# MOSFETboard.net
KiCad netlist of a schematic drawn in EAGLE
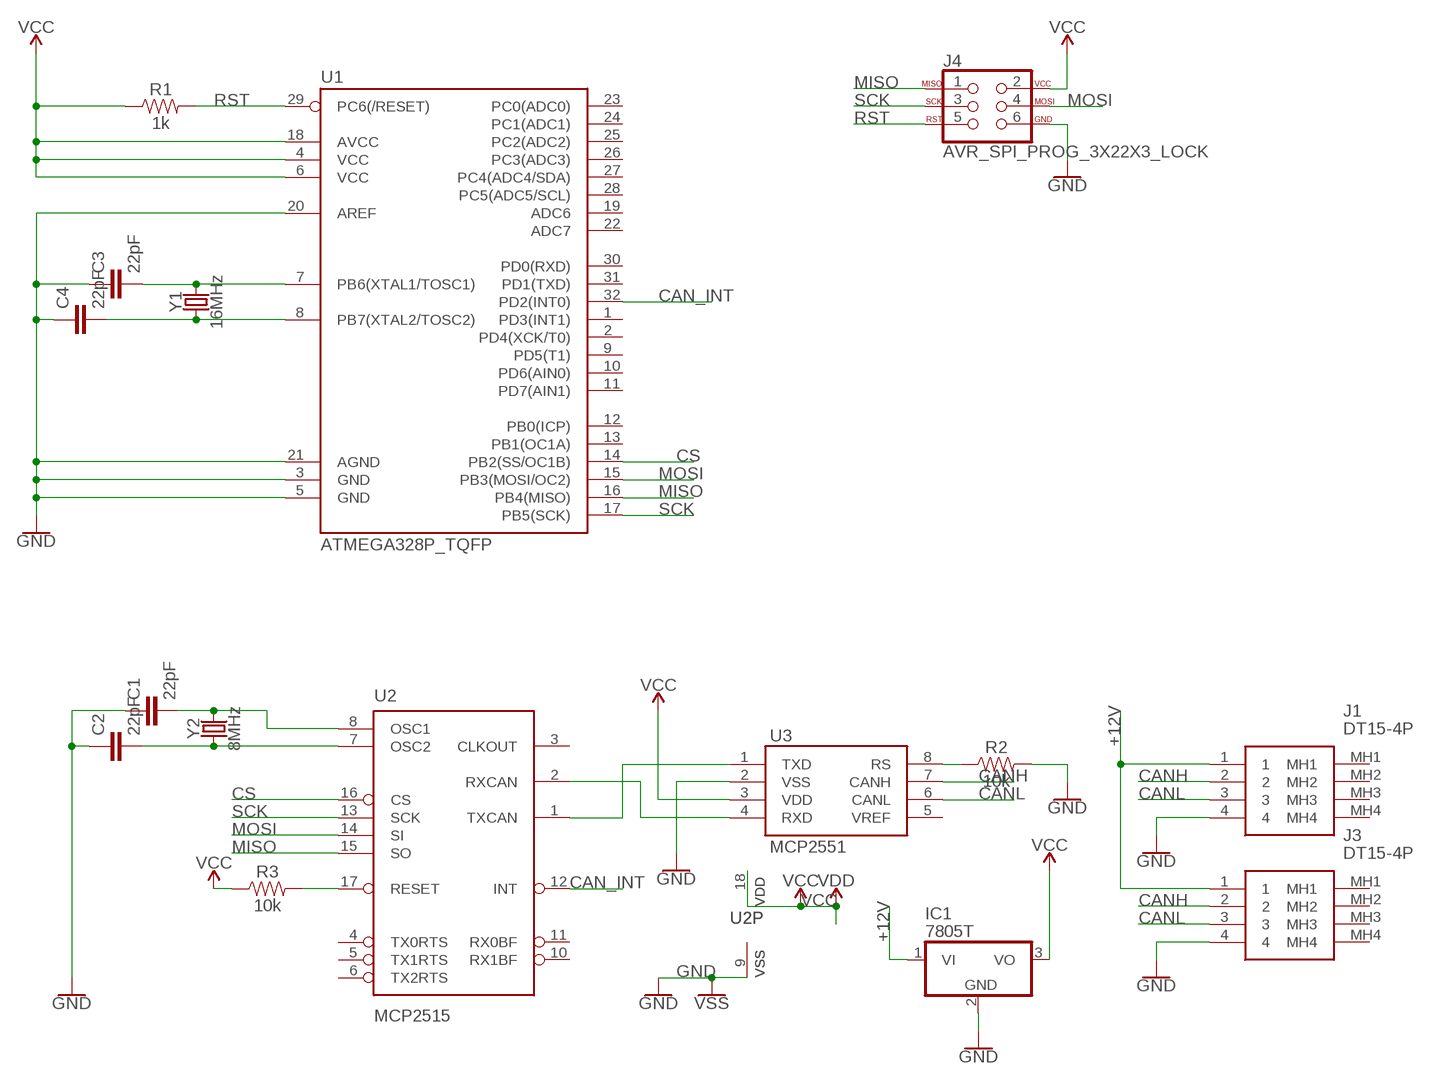
[diagram p0: schematic, sheet 1, part 1 of 2]
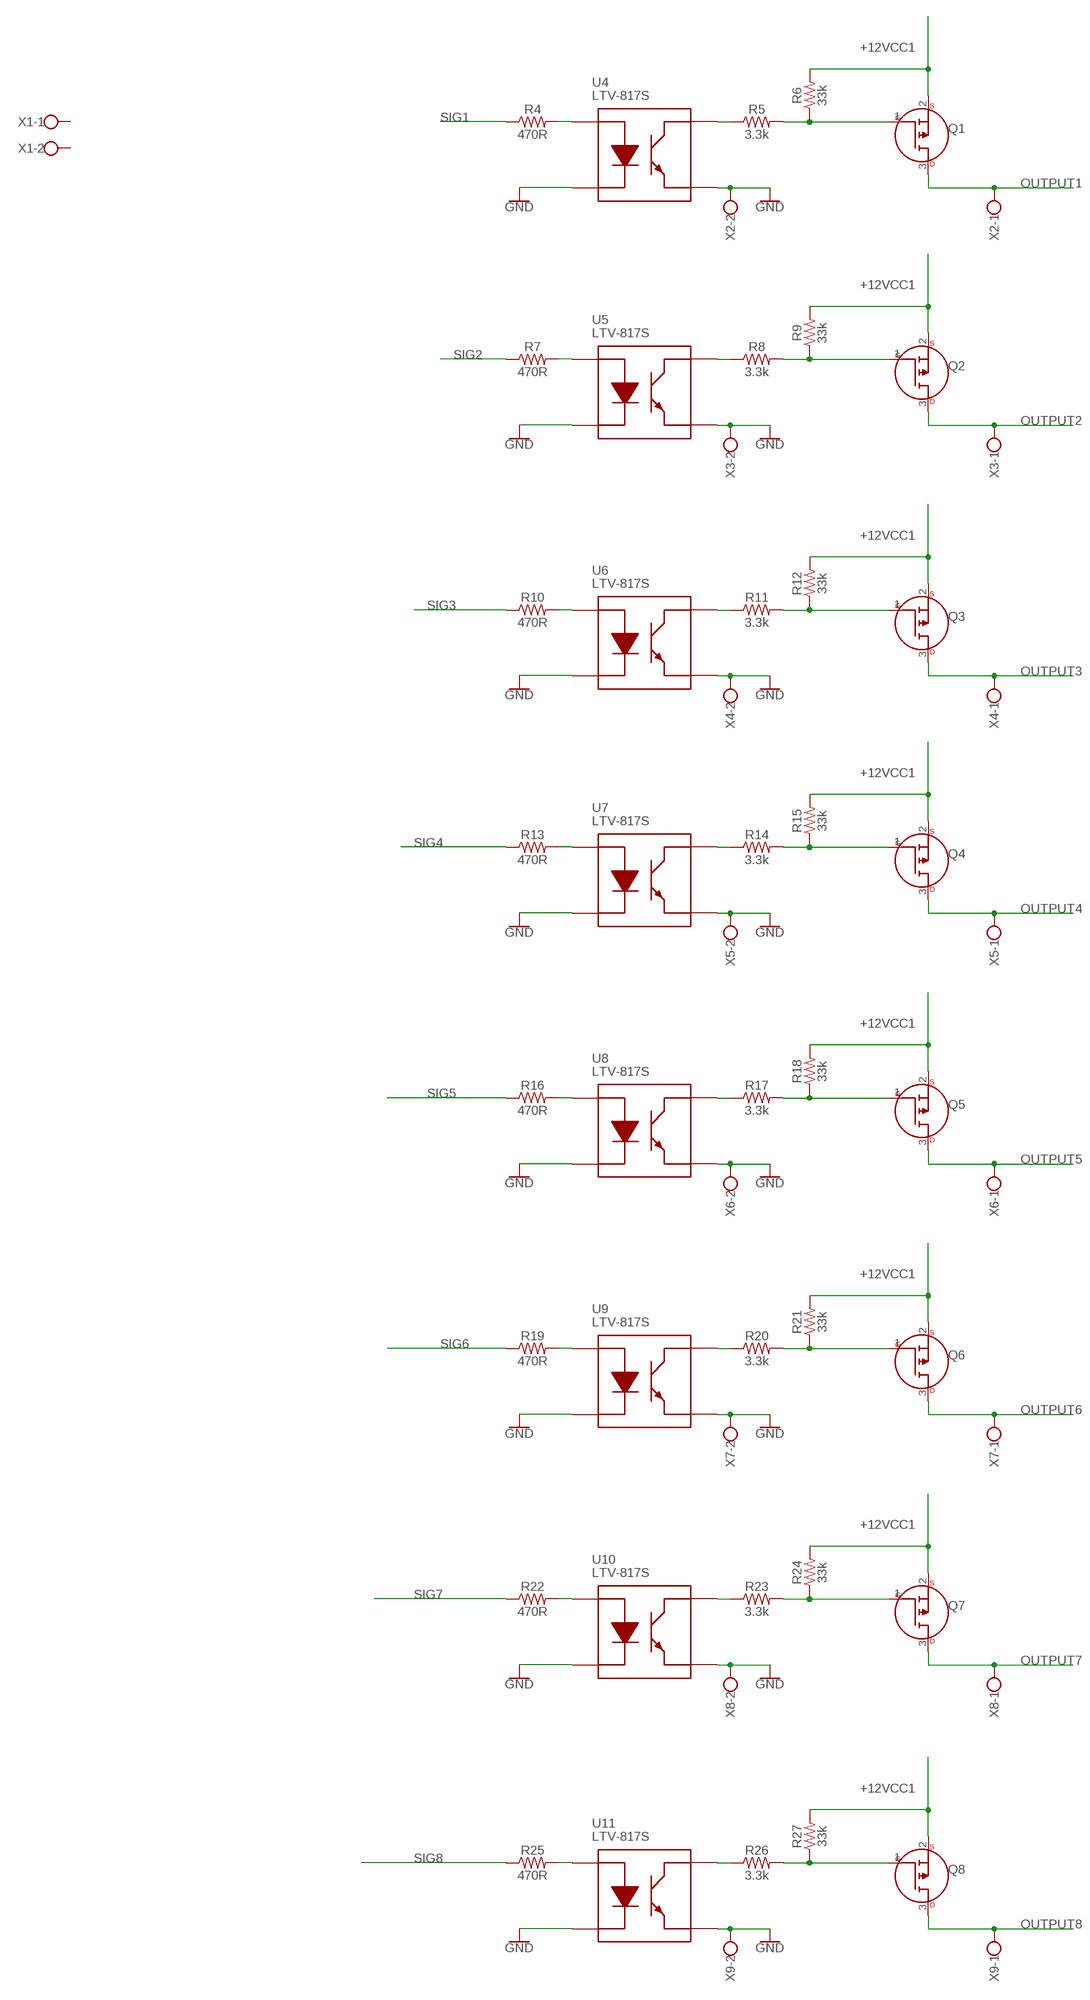
[diagram p1: schematic, sheet 1, part 2 of 2]

(export (version "E")
  (design (tool "Eeschema 10.0.6"))
  (components
    (comp (ref "C1")
      (value "22pF")
      (footprint "eagle-import:0603")
      (libsource (lib "eagle-import") (part "22PF-0603-50V-5%"))
    )
    (comp (ref "C2")
      (value "22pF")
      (footprint "eagle-import:0603")
      (libsource (lib "eagle-import") (part "22PF-0603-50V-5%"))
    )
    (comp (ref "C3")
      (value "22pF")
      (footprint "eagle-import:0603")
      (libsource (lib "eagle-import") (part "22PF-0603-50V-5%"))
    )
    (comp (ref "C4")
      (value "22pF")
      (footprint "eagle-import:0603")
      (libsource (lib "eagle-import") (part "22PF-0603-50V-5%"))
    )
    (comp (ref "IC1")
      (value "7805T")
      (footprint "eagle-import:TO220H")
      (libsource (lib "eagle-import") (part "78T05"))
    )
    (comp (ref "J1")
      (value "DT15-4P")
      (footprint "eagle-import:DT154P")
      (fields (field (name "MOUSER_PART_NUMBER") "571-DT15-4P"))
      (libsource (lib "eagle-import") (part "DT15-4P"))
    )
    (comp (ref "J3")
      (value "DT15-4P")
      (footprint "eagle-import:DT154P")
      (fields (field (name "MOUSER_PART_NUMBER") "571-DT15-4P"))
      (libsource (lib "eagle-import") (part "DT15-4P"))
    )
    (comp (ref "J4")
      (value "AVR_SPI_PROG_3X22X3_LOCK")
      (footprint "eagle-import:2X3_LOCK")
      (libsource (lib "eagle-import") (part "AVR_SPI_PROG_3X22X3_LOCK"))
    )
    (comp (ref "Q1")
      (value "IRFR9014TRPBF-BE3")
      (footprint "eagle-import:IRFR9014TRPBFBE3")
      (fields (field (name "MOUSER_PART_NUMBER") "78-IRFR9014TRPBF-BE3"))
      (libsource (lib "eagle-import") (part "IRFR9014TRPBF-BE3"))
    )
    (comp (ref "Q2")
      (value "IRFR9014TRPBF-BE3")
      (footprint "eagle-import:IRFR9014TRPBFBE3")
      (fields (field (name "MOUSER_PART_NUMBER") "78-IRFR9014TRPBF-BE3"))
      (libsource (lib "eagle-import") (part "IRFR9014TRPBF-BE3"))
    )
    (comp (ref "Q3")
      (value "IRFR9014TRPBF-BE3")
      (footprint "eagle-import:IRFR9014TRPBFBE3")
      (fields (field (name "MOUSER_PART_NUMBER") "78-IRFR9014TRPBF-BE3"))
      (libsource (lib "eagle-import") (part "IRFR9014TRPBF-BE3"))
    )
    (comp (ref "Q4")
      (value "IRFR9014TRPBF-BE3")
      (footprint "eagle-import:IRFR9014TRPBFBE3")
      (fields (field (name "MOUSER_PART_NUMBER") "78-IRFR9014TRPBF-BE3"))
      (libsource (lib "eagle-import") (part "IRFR9014TRPBF-BE3"))
    )
    (comp (ref "Q5")
      (value "IRFR9014TRPBF-BE3")
      (footprint "eagle-import:IRFR9014TRPBFBE3")
      (fields (field (name "MOUSER_PART_NUMBER") "78-IRFR9014TRPBF-BE3"))
      (libsource (lib "eagle-import") (part "IRFR9014TRPBF-BE3"))
    )
    (comp (ref "Q6")
      (value "IRFR9014TRPBF-BE3")
      (footprint "eagle-import:IRFR9014TRPBFBE3")
      (fields (field (name "MOUSER_PART_NUMBER") "78-IRFR9014TRPBF-BE3"))
      (libsource (lib "eagle-import") (part "IRFR9014TRPBF-BE3"))
    )
    (comp (ref "Q7")
      (value "IRFR9014TRPBF-BE3")
      (footprint "eagle-import:IRFR9014TRPBFBE3")
      (fields (field (name "MOUSER_PART_NUMBER") "78-IRFR9014TRPBF-BE3"))
      (libsource (lib "eagle-import") (part "IRFR9014TRPBF-BE3"))
    )
    (comp (ref "Q8")
      (value "IRFR9014TRPBF-BE3")
      (footprint "eagle-import:IRFR9014TRPBFBE3")
      (fields (field (name "MOUSER_PART_NUMBER") "78-IRFR9014TRPBF-BE3"))
      (libsource (lib "eagle-import") (part "IRFR9014TRPBF-BE3"))
    )
    (comp (ref "R1")
      (value "1k")
      (footprint "eagle-import:0603")
      (libsource (lib "eagle-import") (part "1KOHM-0603-1/10W-1%"))
    )
    (comp (ref "R2")
      (value "10k")
      (footprint "eagle-import:0603")
      (libsource (lib "eagle-import") (part "1KOHM-0603-1/10W-1%"))
    )
    (comp (ref "R3")
      (value "10k")
      (footprint "eagle-import:0603")
      (libsource (lib "eagle-import") (part "1KOHM-0603-1/10W-1%"))
    )
    (comp (ref "R4")
      (value "470R")
      (footprint "eagle-import:0603")
      (libsource (lib "eagle-import") (part "1KOHM-0603-1/10W-1%"))
    )
    (comp (ref "R5")
      (value "3.3k")
      (footprint "eagle-import:0603")
      (libsource (lib "eagle-import") (part "1KOHM-0603-1/10W-1%"))
    )
    (comp (ref "R6")
      (value "33k")
      (footprint "eagle-import:0603")
      (libsource (lib "eagle-import") (part "1KOHM-0603-1/10W-1%"))
    )
    (comp (ref "R7")
      (value "470R")
      (footprint "eagle-import:0603")
      (libsource (lib "eagle-import") (part "1KOHM-0603-1/10W-1%"))
    )
    (comp (ref "R8")
      (value "3.3k")
      (footprint "eagle-import:0603")
      (libsource (lib "eagle-import") (part "1KOHM-0603-1/10W-1%"))
    )
    (comp (ref "R9")
      (value "33k")
      (footprint "eagle-import:0603")
      (libsource (lib "eagle-import") (part "1KOHM-0603-1/10W-1%"))
    )
    (comp (ref "R10")
      (value "470R")
      (footprint "eagle-import:0603")
      (libsource (lib "eagle-import") (part "1KOHM-0603-1/10W-1%"))
    )
    (comp (ref "R11")
      (value "3.3k")
      (footprint "eagle-import:0603")
      (libsource (lib "eagle-import") (part "1KOHM-0603-1/10W-1%"))
    )
    (comp (ref "R12")
      (value "33k")
      (footprint "eagle-import:0603")
      (libsource (lib "eagle-import") (part "1KOHM-0603-1/10W-1%"))
    )
    (comp (ref "R13")
      (value "470R")
      (footprint "eagle-import:0603")
      (libsource (lib "eagle-import") (part "1KOHM-0603-1/10W-1%"))
    )
    (comp (ref "R14")
      (value "3.3k")
      (footprint "eagle-import:0603")
      (libsource (lib "eagle-import") (part "1KOHM-0603-1/10W-1%"))
    )
    (comp (ref "R15")
      (value "33k")
      (footprint "eagle-import:0603")
      (libsource (lib "eagle-import") (part "1KOHM-0603-1/10W-1%"))
    )
    (comp (ref "R16")
      (value "470R")
      (footprint "eagle-import:0603")
      (libsource (lib "eagle-import") (part "1KOHM-0603-1/10W-1%"))
    )
    (comp (ref "R17")
      (value "3.3k")
      (footprint "eagle-import:0603")
      (libsource (lib "eagle-import") (part "1KOHM-0603-1/10W-1%"))
    )
    (comp (ref "R18")
      (value "33k")
      (footprint "eagle-import:0603")
      (libsource (lib "eagle-import") (part "1KOHM-0603-1/10W-1%"))
    )
    (comp (ref "R19")
      (value "470R")
      (footprint "eagle-import:0603")
      (libsource (lib "eagle-import") (part "1KOHM-0603-1/10W-1%"))
    )
    (comp (ref "R20")
      (value "3.3k")
      (footprint "eagle-import:0603")
      (libsource (lib "eagle-import") (part "1KOHM-0603-1/10W-1%"))
    )
    (comp (ref "R21")
      (value "33k")
      (footprint "eagle-import:0603")
      (libsource (lib "eagle-import") (part "1KOHM-0603-1/10W-1%"))
    )
    (comp (ref "R22")
      (value "470R")
      (footprint "eagle-import:0603")
      (libsource (lib "eagle-import") (part "1KOHM-0603-1/10W-1%"))
    )
    (comp (ref "R23")
      (value "3.3k")
      (footprint "eagle-import:0603")
      (libsource (lib "eagle-import") (part "1KOHM-0603-1/10W-1%"))
    )
    (comp (ref "R24")
      (value "33k")
      (footprint "eagle-import:0603")
      (libsource (lib "eagle-import") (part "1KOHM-0603-1/10W-1%"))
    )
    (comp (ref "R25")
      (value "470R")
      (footprint "eagle-import:0603")
      (libsource (lib "eagle-import") (part "1KOHM-0603-1/10W-1%"))
    )
    (comp (ref "R26")
      (value "3.3k")
      (footprint "eagle-import:0603")
      (libsource (lib "eagle-import") (part "1KOHM-0603-1/10W-1%"))
    )
    (comp (ref "R27")
      (value "33k")
      (footprint "eagle-import:0603")
      (libsource (lib "eagle-import") (part "1KOHM-0603-1/10W-1%"))
    )
    (comp (ref "U1")
      (value "ATMEGA328P_TQFP")
      (footprint "eagle-import:TQFP32-08")
      (libsource (lib "eagle-import") (part "ATMEGA328P_TQFP"))
    )
    (comp (ref "U2")
      (value "MCP2515")
      (footprint "eagle-import:SO18W")
      (libsource (lib "eagle-import") (part "MCP2515(MCP2510)SO"))
    )
    (comp (ref "U3")
      (value "MCP2551")
      (footprint "eagle-import:SO08")
      (libsource (lib "eagle-import") (part "MCP2551"))
    )
    (comp (ref "U4")
      (value "LTV-817S")
      (footprint "eagle-import:SOP254P1016X460-4N")
      (fields (field (name "MOUSER_PART_NUMBER") "859-LTV-817S"))
      (libsource (lib "eagle-import") (part "LTV-817S"))
    )
    (comp (ref "U5")
      (value "LTV-817S")
      (footprint "eagle-import:SOP254P1016X460-4N")
      (fields (field (name "MOUSER_PART_NUMBER") "859-LTV-817S"))
      (libsource (lib "eagle-import") (part "LTV-817S"))
    )
    (comp (ref "U6")
      (value "LTV-817S")
      (footprint "eagle-import:SOP254P1016X460-4N")
      (fields (field (name "MOUSER_PART_NUMBER") "859-LTV-817S"))
      (libsource (lib "eagle-import") (part "LTV-817S"))
    )
    (comp (ref "U7")
      (value "LTV-817S")
      (footprint "eagle-import:SOP254P1016X460-4N")
      (fields (field (name "MOUSER_PART_NUMBER") "859-LTV-817S"))
      (libsource (lib "eagle-import") (part "LTV-817S"))
    )
    (comp (ref "U8")
      (value "LTV-817S")
      (footprint "eagle-import:SOP254P1016X460-4N")
      (fields (field (name "MOUSER_PART_NUMBER") "859-LTV-817S"))
      (libsource (lib "eagle-import") (part "LTV-817S"))
    )
    (comp (ref "U9")
      (value "LTV-817S")
      (footprint "eagle-import:SOP254P1016X460-4N")
      (fields (field (name "MOUSER_PART_NUMBER") "859-LTV-817S"))
      (libsource (lib "eagle-import") (part "LTV-817S"))
    )
    (comp (ref "U10")
      (value "LTV-817S")
      (footprint "eagle-import:SOP254P1016X460-4N")
      (fields (field (name "MOUSER_PART_NUMBER") "859-LTV-817S"))
      (libsource (lib "eagle-import") (part "LTV-817S"))
    )
    (comp (ref "U11")
      (value "LTV-817S")
      (footprint "eagle-import:SOP254P1016X460-4N")
      (fields (field (name "MOUSER_PART_NUMBER") "859-LTV-817S"))
      (libsource (lib "eagle-import") (part "LTV-817S"))
    )
    (comp (ref "X1")
      (value "W237-102")
      (footprint "eagle-import:W237-102")
      (fields (field (name "MPN") "237-102"))
      (libsource (lib "eagle-import") (part "W237-102"))
    )
    (comp (ref "X2")
      (value "W237-102")
      (footprint "eagle-import:W237-102")
      (fields (field (name "MPN") "237-102"))
      (libsource (lib "eagle-import") (part "W237-102"))
    )
    (comp (ref "X3")
      (value "W237-102")
      (footprint "eagle-import:W237-102")
      (fields (field (name "MPN") "237-102"))
      (libsource (lib "eagle-import") (part "W237-102"))
    )
    (comp (ref "X4")
      (value "W237-102")
      (footprint "eagle-import:W237-102")
      (fields (field (name "MPN") "237-102"))
      (libsource (lib "eagle-import") (part "W237-102"))
    )
    (comp (ref "X5")
      (value "W237-102")
      (footprint "eagle-import:W237-102")
      (fields (field (name "MPN") "237-102"))
      (libsource (lib "eagle-import") (part "W237-102"))
    )
    (comp (ref "X6")
      (value "W237-102")
      (footprint "eagle-import:W237-102")
      (fields (field (name "MPN") "237-102"))
      (libsource (lib "eagle-import") (part "W237-102"))
    )
    (comp (ref "X7")
      (value "W237-102")
      (footprint "eagle-import:W237-102")
      (fields (field (name "MPN") "237-102"))
      (libsource (lib "eagle-import") (part "W237-102"))
    )
    (comp (ref "X8")
      (value "W237-102")
      (footprint "eagle-import:W237-102")
      (fields (field (name "MPN") "237-102"))
      (libsource (lib "eagle-import") (part "W237-102"))
    )
    (comp (ref "X9")
      (value "W237-102")
      (footprint "eagle-import:W237-102")
      (fields (field (name "MPN") "237-102"))
      (libsource (lib "eagle-import") (part "W237-102"))
    )
    (comp (ref "Y1")
      (value "16MHz")
      (footprint "eagle-import:HC49UP")
      (libsource (lib "eagle-import") (part "CRYSTAL-8MHZSMD-HC49UP"))
    )
    (comp (ref "Y2")
      (value "8MHz")
      (footprint "eagle-import:HC49UP")
      (libsource (lib "eagle-import") (part "CRYSTAL-8MHZSMD-HC49UP"))
    )
  )
  (nets
    (net (code "1") (name "/+12V") (class "Default")
      (node (ref "IC1") (pin "1") (pinfunction "VI_1") (pintype "input"))
      (node (ref "J1") (pin "1") (pinfunction "1_1") (pintype "bidirectional"))
      (node (ref "J3") (pin "1") (pinfunction "1_1") (pintype "bidirectional"))
    )
    (net (code "2") (name "/+12VCC1") (class "Default")
      (node (ref "Q1") (pin "2") (pinfunction "D_2") (pintype "bidirectional"))
      (node (ref "Q2") (pin "2") (pinfunction "D_2") (pintype "bidirectional"))
      (node (ref "Q3") (pin "2") (pinfunction "D_2") (pintype "bidirectional"))
      (node (ref "Q4") (pin "2") (pinfunction "D_2") (pintype "bidirectional"))
      (node (ref "Q5") (pin "2") (pinfunction "D_2") (pintype "bidirectional"))
      (node (ref "Q6") (pin "2") (pinfunction "D_2") (pintype "bidirectional"))
      (node (ref "Q7") (pin "2") (pinfunction "D_2") (pintype "bidirectional"))
      (node (ref "Q8") (pin "2") (pinfunction "D_2") (pintype "bidirectional"))
      (node (ref "R12") (pin "2") (pinfunction "2_2") (pintype "passive"))
      (node (ref "R15") (pin "2") (pinfunction "2_2") (pintype "passive"))
      (node (ref "R18") (pin "2") (pinfunction "2_2") (pintype "passive"))
      (node (ref "R21") (pin "2") (pinfunction "2_2") (pintype "passive"))
      (node (ref "R24") (pin "2") (pinfunction "2_2") (pintype "passive"))
      (node (ref "R27") (pin "2") (pinfunction "2_2") (pintype "passive"))
      (node (ref "R6") (pin "2") (pinfunction "2_2") (pintype "passive"))
      (node (ref "R9") (pin "2") (pinfunction "2_2") (pintype "passive"))
    )
    (net (code "3") (name "/CANH") (class "Default")
      (node (ref "J1") (pin "2") (pinfunction "2_2") (pintype "bidirectional"))
      (node (ref "J3") (pin "2") (pinfunction "2_2") (pintype "bidirectional"))
      (node (ref "U3") (pin "7") (pinfunction "CANH_7") (pintype "bidirectional"))
    )
    (net (code "4") (name "/CANL") (class "Default")
      (node (ref "J1") (pin "3") (pinfunction "3_3") (pintype "bidirectional"))
      (node (ref "J3") (pin "3") (pinfunction "3_3") (pintype "bidirectional"))
      (node (ref "U3") (pin "6") (pinfunction "CANL_6") (pintype "bidirectional"))
    )
    (net (code "5") (name "/CAN_INT") (class "Default")
      (node (ref "U1") (pin "32") (pinfunction "PD2(INT0)_32") (pintype "bidirectional"))
      (node (ref "U2") (pin "12") (pinfunction "INT_12") (pintype "output"))
    )
    (net (code "6") (name "/CS") (class "Default")
      (node (ref "U1") (pin "14") (pinfunction "PB2(SS/OC1B)_14") (pintype "bidirectional"))
      (node (ref "U2") (pin "16") (pinfunction "CS_16") (pintype "input"))
    )
    (net (code "7") (name "/MISO") (class "Default")
      (node (ref "J4") (pin "1") (pinfunction "1_1") (pintype "passive"))
      (node (ref "U1") (pin "16") (pinfunction "PB4(MISO)_16") (pintype "bidirectional"))
      (node (ref "U2") (pin "15") (pinfunction "SO_15") (pintype "output"))
    )
    (net (code "8") (name "/MOSI") (class "Default")
      (node (ref "J4") (pin "4") (pinfunction "4_4") (pintype "passive"))
      (node (ref "U1") (pin "15") (pinfunction "PB3(MOSI/OC2)_15") (pintype "bidirectional"))
      (node (ref "U2") (pin "14") (pinfunction "SI_14") (pintype "input"))
    )
    (net (code "9") (name "/OUTPUT1") (class "Default")
      (node (ref "Q1") (pin "3") (pinfunction "S_3") (pintype "bidirectional"))
      (node (ref "X2") (pin "1") (pinfunction "KL_1") (pintype "passive"))
    )
    (net (code "10") (name "/OUTPUT2") (class "Default")
      (node (ref "Q2") (pin "3") (pinfunction "S_3") (pintype "bidirectional"))
      (node (ref "X3") (pin "1") (pinfunction "KL_1") (pintype "passive"))
    )
    (net (code "11") (name "/OUTPUT3") (class "Default")
      (node (ref "Q3") (pin "3") (pinfunction "S_3") (pintype "bidirectional"))
      (node (ref "X4") (pin "1") (pinfunction "KL_1") (pintype "passive"))
    )
    (net (code "12") (name "/OUTPUT4") (class "Default")
      (node (ref "Q4") (pin "3") (pinfunction "S_3") (pintype "bidirectional"))
      (node (ref "X5") (pin "1") (pinfunction "KL_1") (pintype "passive"))
    )
    (net (code "13") (name "/OUTPUT5") (class "Default")
      (node (ref "Q5") (pin "3") (pinfunction "S_3") (pintype "bidirectional"))
      (node (ref "X6") (pin "1") (pinfunction "KL_1") (pintype "passive"))
    )
    (net (code "14") (name "/OUTPUT6") (class "Default")
      (node (ref "Q6") (pin "3") (pinfunction "S_3") (pintype "bidirectional"))
      (node (ref "X7") (pin "1") (pinfunction "KL_1") (pintype "passive"))
    )
    (net (code "15") (name "/OUTPUT7") (class "Default")
      (node (ref "Q7") (pin "3") (pinfunction "S_3") (pintype "bidirectional"))
      (node (ref "X8") (pin "1") (pinfunction "KL_1") (pintype "passive"))
    )
    (net (code "16") (name "/OUTPUT8") (class "Default")
      (node (ref "Q8") (pin "3") (pinfunction "S_3") (pintype "bidirectional"))
      (node (ref "X9") (pin "1") (pinfunction "KL_1") (pintype "passive"))
    )
    (net (code "17") (name "/RST") (class "Default")
      (node (ref "J4") (pin "5") (pinfunction "5_5") (pintype "passive"))
      (node (ref "R1") (pin "2") (pinfunction "2_2") (pintype "passive"))
      (node (ref "U1") (pin "29") (pinfunction "PC6(/RESET)_29") (pintype "bidirectional"))
    )
    (net (code "18") (name "/SCK") (class "Default")
      (node (ref "J4") (pin "3") (pinfunction "3_3") (pintype "passive"))
      (node (ref "U1") (pin "17") (pinfunction "PB5(SCK)_17") (pintype "bidirectional"))
      (node (ref "U2") (pin "13") (pinfunction "SCK_13") (pintype "input"))
    )
    (net (code "19") (name "/SIG1") (class "Default")
      (node (ref "R4") (pin "1") (pinfunction "1_1") (pintype "passive"))
    )
    (net (code "20") (name "/SIG2") (class "Default")
      (node (ref "R7") (pin "1") (pinfunction "1_1") (pintype "passive"))
    )
    (net (code "21") (name "/SIG3") (class "Default")
      (node (ref "R10") (pin "1") (pinfunction "1_1") (pintype "passive"))
    )
    (net (code "22") (name "/SIG4") (class "Default")
      (node (ref "R13") (pin "1") (pinfunction "1_1") (pintype "passive"))
    )
    (net (code "23") (name "/SIG5") (class "Default")
      (node (ref "R16") (pin "1") (pinfunction "1_1") (pintype "passive"))
    )
    (net (code "24") (name "/SIG6") (class "Default")
      (node (ref "R19") (pin "1") (pinfunction "1_1") (pintype "passive"))
    )
    (net (code "25") (name "/SIG7") (class "Default")
      (node (ref "R22") (pin "1") (pinfunction "1_1") (pintype "passive"))
    )
    (net (code "26") (name "/SIG8") (class "Default")
      (node (ref "R25") (pin "1") (pinfunction "1_1") (pintype "passive"))
    )
    (net (code "27") (name "GND") (class "Default")
      (node (ref "C1") (pin "1") (pinfunction "1_1") (pintype "passive"))
      (node (ref "C2") (pin "1") (pinfunction "1_1") (pintype "passive"))
      (node (ref "C3") (pin "1") (pinfunction "1_1") (pintype "passive"))
      (node (ref "C4") (pin "1") (pinfunction "1_1") (pintype "passive"))
      (node (ref "IC1") (pin "2") (pinfunction "GND_2") (pintype "passive"))
      (node (ref "J1") (pin "4") (pinfunction "4_4") (pintype "bidirectional"))
      (node (ref "J3") (pin "4") (pinfunction "4_4") (pintype "bidirectional"))
      (node (ref "J4") (pin "6") (pinfunction "6_6") (pintype "passive"))
      (node (ref "R2") (pin "2") (pinfunction "2_2") (pintype "passive"))
      (node (ref "U1") (pin "20") (pinfunction "AREF_20") (pintype "bidirectional"))
      (node (ref "U1") (pin "21") (pinfunction "AGND_21") (pintype "bidirectional"))
      (node (ref "U1") (pin "3") (pinfunction "GND_3") (pintype "bidirectional"))
      (node (ref "U1") (pin "5") (pinfunction "GND_5") (pintype "bidirectional"))
      (node (ref "U10") (pin "2") (pinfunction "CATHODE_2") (pintype "bidirectional"))
      (node (ref "U10") (pin "3") (pinfunction "EMITTER_3") (pintype "bidirectional"))
      (node (ref "U11") (pin "2") (pinfunction "CATHODE_2") (pintype "bidirectional"))
      (node (ref "U11") (pin "3") (pinfunction "EMITTER_3") (pintype "bidirectional"))
      (node (ref "U2") (pin "9") (pinfunction "VSS_9") (pintype "power_in"))
      (node (ref "U3") (pin "2") (pinfunction "VSS_2") (pintype "bidirectional"))
      (node (ref "U4") (pin "2") (pinfunction "CATHODE_2") (pintype "bidirectional"))
      (node (ref "U4") (pin "3") (pinfunction "EMITTER_3") (pintype "bidirectional"))
      (node (ref "U5") (pin "2") (pinfunction "CATHODE_2") (pintype "bidirectional"))
      (node (ref "U5") (pin "3") (pinfunction "EMITTER_3") (pintype "bidirectional"))
      (node (ref "U6") (pin "2") (pinfunction "CATHODE_2") (pintype "bidirectional"))
      (node (ref "U6") (pin "3") (pinfunction "EMITTER_3") (pintype "bidirectional"))
      (node (ref "U7") (pin "2") (pinfunction "CATHODE_2") (pintype "bidirectional"))
      (node (ref "U7") (pin "3") (pinfunction "EMITTER_3") (pintype "bidirectional"))
      (node (ref "U8") (pin "2") (pinfunction "CATHODE_2") (pintype "bidirectional"))
      (node (ref "U8") (pin "3") (pinfunction "EMITTER_3") (pintype "bidirectional"))
      (node (ref "U9") (pin "2") (pinfunction "CATHODE_2") (pintype "bidirectional"))
      (node (ref "U9") (pin "3") (pinfunction "EMITTER_3") (pintype "bidirectional"))
      (node (ref "X2") (pin "2") (pinfunction "KL_2") (pintype "passive"))
      (node (ref "X3") (pin "2") (pinfunction "KL_2") (pintype "passive"))
      (node (ref "X4") (pin "2") (pinfunction "KL_2") (pintype "passive"))
      (node (ref "X5") (pin "2") (pinfunction "KL_2") (pintype "passive"))
      (node (ref "X6") (pin "2") (pinfunction "KL_2") (pintype "passive"))
      (node (ref "X7") (pin "2") (pinfunction "KL_2") (pintype "passive"))
      (node (ref "X8") (pin "2") (pinfunction "KL_2") (pintype "passive"))
      (node (ref "X9") (pin "2") (pinfunction "KL_2") (pintype "passive"))
    )
    (net (code "28") (name "Net-(Q1-G)") (class "Default")
      (node (ref "Q1") (pin "1") (pinfunction "G_1") (pintype "bidirectional"))
      (node (ref "R5") (pin "2") (pinfunction "2_2") (pintype "passive"))
      (node (ref "R6") (pin "1") (pinfunction "1_1") (pintype "passive"))
    )
    (net (code "29") (name "Net-(Q2-G)") (class "Default")
      (node (ref "Q2") (pin "1") (pinfunction "G_1") (pintype "bidirectional"))
      (node (ref "R8") (pin "2") (pinfunction "2_2") (pintype "passive"))
      (node (ref "R9") (pin "1") (pinfunction "1_1") (pintype "passive"))
    )
    (net (code "30") (name "Net-(Q3-G)") (class "Default")
      (node (ref "Q3") (pin "1") (pinfunction "G_1") (pintype "bidirectional"))
      (node (ref "R11") (pin "2") (pinfunction "2_2") (pintype "passive"))
      (node (ref "R12") (pin "1") (pinfunction "1_1") (pintype "passive"))
    )
    (net (code "31") (name "Net-(Q4-G)") (class "Default")
      (node (ref "Q4") (pin "1") (pinfunction "G_1") (pintype "bidirectional"))
      (node (ref "R14") (pin "2") (pinfunction "2_2") (pintype "passive"))
      (node (ref "R15") (pin "1") (pinfunction "1_1") (pintype "passive"))
    )
    (net (code "32") (name "Net-(Q5-G)") (class "Default")
      (node (ref "Q5") (pin "1") (pinfunction "G_1") (pintype "bidirectional"))
      (node (ref "R17") (pin "2") (pinfunction "2_2") (pintype "passive"))
      (node (ref "R18") (pin "1") (pinfunction "1_1") (pintype "passive"))
    )
    (net (code "33") (name "Net-(Q6-G)") (class "Default")
      (node (ref "Q6") (pin "1") (pinfunction "G_1") (pintype "bidirectional"))
      (node (ref "R20") (pin "2") (pinfunction "2_2") (pintype "passive"))
      (node (ref "R21") (pin "1") (pinfunction "1_1") (pintype "passive"))
    )
    (net (code "34") (name "Net-(Q7-G)") (class "Default")
      (node (ref "Q7") (pin "1") (pinfunction "G_1") (pintype "bidirectional"))
      (node (ref "R23") (pin "2") (pinfunction "2_2") (pintype "passive"))
      (node (ref "R24") (pin "1") (pinfunction "1_1") (pintype "passive"))
    )
    (net (code "35") (name "Net-(Q8-G)") (class "Default")
      (node (ref "Q8") (pin "1") (pinfunction "G_1") (pintype "bidirectional"))
      (node (ref "R26") (pin "2") (pinfunction "2_2") (pintype "passive"))
      (node (ref "R27") (pin "1") (pinfunction "1_1") (pintype "passive"))
    )
    (net (code "36") (name "Net-(U1-PB6(XTAL1{slash}TOSC1))") (class "Default")
      (node (ref "C3") (pin "2") (pinfunction "2_2") (pintype "passive"))
      (node (ref "U1") (pin "7") (pinfunction "PB6(XTAL1/TOSC1)_7") (pintype "bidirectional"))
      (node (ref "Y1") (pin "2") (pinfunction "2_2") (pintype "passive"))
    )
    (net (code "37") (name "Net-(U1-PB7(XTAL2{slash}TOSC2))") (class "Default")
      (node (ref "C4") (pin "2") (pinfunction "2_2") (pintype "passive"))
      (node (ref "U1") (pin "8") (pinfunction "PB7(XTAL2/TOSC2)_8") (pintype "bidirectional"))
      (node (ref "Y1") (pin "1") (pinfunction "1_1") (pintype "passive"))
    )
    (net (code "38") (name "Net-(U2A-OSC1)") (class "Default")
      (node (ref "C1") (pin "2") (pinfunction "2_2") (pintype "passive"))
      (node (ref "U2") (pin "8") (pinfunction "OSC1_8") (pintype "input"))
      (node (ref "Y2") (pin "2") (pinfunction "2_2") (pintype "passive"))
    )
    (net (code "39") (name "Net-(U2A-OSC2)") (class "Default")
      (node (ref "C2") (pin "2") (pinfunction "2_2") (pintype "passive"))
      (node (ref "U2") (pin "7") (pinfunction "OSC2_7") (pintype "output"))
      (node (ref "Y2") (pin "1") (pinfunction "1_1") (pintype "passive"))
    )
    (net (code "40") (name "Net-(U2A-RESET)") (class "Default")
      (node (ref "R3") (pin "2") (pinfunction "2_2") (pintype "passive"))
      (node (ref "U2") (pin "17") (pinfunction "RESET_17") (pintype "input"))
    )
    (net (code "41") (name "Net-(U2A-RXCAN)") (class "Default")
      (node (ref "U2") (pin "2") (pinfunction "RXCAN_2") (pintype "input"))
      (node (ref "U3") (pin "4") (pinfunction "RXD_4") (pintype "bidirectional"))
    )
    (net (code "42") (name "Net-(U2A-TXCAN)") (class "Default")
      (node (ref "U2") (pin "1") (pinfunction "TXCAN_1") (pintype "output"))
      (node (ref "U3") (pin "1") (pinfunction "TXD_1") (pintype "bidirectional"))
    )
    (net (code "43") (name "Net-(U3-RS)") (class "Default")
      (node (ref "R2") (pin "1") (pinfunction "1_1") (pintype "passive"))
      (node (ref "U3") (pin "8") (pinfunction "RS_8") (pintype "bidirectional"))
    )
    (net (code "44") (name "Net-(U4-ANODE)") (class "Default")
      (node (ref "R4") (pin "2") (pinfunction "2_2") (pintype "passive"))
      (node (ref "U4") (pin "1") (pinfunction "ANODE_1") (pintype "bidirectional"))
    )
    (net (code "45") (name "Net-(U4-COLLECTOR)") (class "Default")
      (node (ref "R5") (pin "1") (pinfunction "1_1") (pintype "passive"))
      (node (ref "U4") (pin "4") (pinfunction "COLLECTOR_4") (pintype "bidirectional"))
    )
    (net (code "46") (name "Net-(U5-ANODE)") (class "Default")
      (node (ref "R7") (pin "2") (pinfunction "2_2") (pintype "passive"))
      (node (ref "U5") (pin "1") (pinfunction "ANODE_1") (pintype "bidirectional"))
    )
    (net (code "47") (name "Net-(U5-COLLECTOR)") (class "Default")
      (node (ref "R8") (pin "1") (pinfunction "1_1") (pintype "passive"))
      (node (ref "U5") (pin "4") (pinfunction "COLLECTOR_4") (pintype "bidirectional"))
    )
    (net (code "48") (name "Net-(U6-ANODE)") (class "Default")
      (node (ref "R10") (pin "2") (pinfunction "2_2") (pintype "passive"))
      (node (ref "U6") (pin "1") (pinfunction "ANODE_1") (pintype "bidirectional"))
    )
    (net (code "49") (name "Net-(U6-COLLECTOR)") (class "Default")
      (node (ref "R11") (pin "1") (pinfunction "1_1") (pintype "passive"))
      (node (ref "U6") (pin "4") (pinfunction "COLLECTOR_4") (pintype "bidirectional"))
    )
    (net (code "50") (name "Net-(U7-ANODE)") (class "Default")
      (node (ref "R13") (pin "2") (pinfunction "2_2") (pintype "passive"))
      (node (ref "U7") (pin "1") (pinfunction "ANODE_1") (pintype "bidirectional"))
    )
    (net (code "51") (name "Net-(U7-COLLECTOR)") (class "Default")
      (node (ref "R14") (pin "1") (pinfunction "1_1") (pintype "passive"))
      (node (ref "U7") (pin "4") (pinfunction "COLLECTOR_4") (pintype "bidirectional"))
    )
    (net (code "52") (name "Net-(U8-ANODE)") (class "Default")
      (node (ref "R16") (pin "2") (pinfunction "2_2") (pintype "passive"))
      (node (ref "U8") (pin "1") (pinfunction "ANODE_1") (pintype "bidirectional"))
    )
    (net (code "53") (name "Net-(U8-COLLECTOR)") (class "Default")
      (node (ref "R17") (pin "1") (pinfunction "1_1") (pintype "passive"))
      (node (ref "U8") (pin "4") (pinfunction "COLLECTOR_4") (pintype "bidirectional"))
    )
    (net (code "54") (name "Net-(U9-ANODE)") (class "Default")
      (node (ref "R19") (pin "2") (pinfunction "2_2") (pintype "passive"))
      (node (ref "U9") (pin "1") (pinfunction "ANODE_1") (pintype "bidirectional"))
    )
    (net (code "55") (name "Net-(U9-COLLECTOR)") (class "Default")
      (node (ref "R20") (pin "1") (pinfunction "1_1") (pintype "passive"))
      (node (ref "U9") (pin "4") (pinfunction "COLLECTOR_4") (pintype "bidirectional"))
    )
    (net (code "56") (name "Net-(U10-ANODE)") (class "Default")
      (node (ref "R22") (pin "2") (pinfunction "2_2") (pintype "passive"))
      (node (ref "U10") (pin "1") (pinfunction "ANODE_1") (pintype "bidirectional"))
    )
    (net (code "57") (name "Net-(U10-COLLECTOR)") (class "Default")
      (node (ref "R23") (pin "1") (pinfunction "1_1") (pintype "passive"))
      (node (ref "U10") (pin "4") (pinfunction "COLLECTOR_4") (pintype "bidirectional"))
    )
    (net (code "58") (name "Net-(U11-ANODE)") (class "Default")
      (node (ref "R25") (pin "2") (pinfunction "2_2") (pintype "passive"))
      (node (ref "U11") (pin "1") (pinfunction "ANODE_1") (pintype "bidirectional"))
    )
    (net (code "59") (name "Net-(U11-COLLECTOR)") (class "Default")
      (node (ref "R26") (pin "1") (pinfunction "1_1") (pintype "passive"))
      (node (ref "U11") (pin "4") (pinfunction "COLLECTOR_4") (pintype "bidirectional"))
    )
    (net (code "60") (name "VCC") (class "Default")
      (node (ref "IC1") (pin "3") (pinfunction "VO_3") (pintype "passive"))
      (node (ref "J4") (pin "2") (pinfunction "2_2") (pintype "passive"))
      (node (ref "R1") (pin "1") (pinfunction "1_1") (pintype "passive"))
      (node (ref "R3") (pin "1") (pinfunction "1_1") (pintype "passive"))
      (node (ref "U1") (pin "18") (pinfunction "AVCC_18") (pintype "bidirectional"))
      (node (ref "U1") (pin "4") (pinfunction "VCC_4") (pintype "bidirectional"))
      (node (ref "U1") (pin "6") (pinfunction "VCC_6") (pintype "bidirectional"))
      (node (ref "U2") (pin "18") (pinfunction "VDD_18") (pintype "power_in"))
      (node (ref "U3") (pin "3") (pinfunction "VDD_3") (pintype "bidirectional"))
    )
    (net (code "61") (name "unconnected-(J1-PadMH1)") (class "Default")
      (node (ref "J1") (pin "MH1") (pinfunction "MH1_MH1") (pintype "bidirectional"))
    )
    (net (code "62") (name "unconnected-(J1-PadMH2)") (class "Default")
      (node (ref "J1") (pin "MH2") (pinfunction "MH2_MH2") (pintype "bidirectional"))
    )
    (net (code "63") (name "unconnected-(J1-PadMH3)") (class "Default")
      (node (ref "J1") (pin "MH3") (pinfunction "MH3_MH3") (pintype "bidirectional"))
    )
    (net (code "64") (name "unconnected-(J1-PadMH4)") (class "Default")
      (node (ref "J1") (pin "MH4") (pinfunction "MH4_MH4") (pintype "bidirectional"))
    )
    (net (code "65") (name "unconnected-(J3-PadMH1)") (class "Default")
      (node (ref "J3") (pin "MH1") (pinfunction "MH1_MH1") (pintype "bidirectional"))
    )
    (net (code "66") (name "unconnected-(J3-PadMH2)") (class "Default")
      (node (ref "J3") (pin "MH2") (pinfunction "MH2_MH2") (pintype "bidirectional"))
    )
    (net (code "67") (name "unconnected-(J3-PadMH3)") (class "Default")
      (node (ref "J3") (pin "MH3") (pinfunction "MH3_MH3") (pintype "bidirectional"))
    )
    (net (code "68") (name "unconnected-(J3-PadMH4)") (class "Default")
      (node (ref "J3") (pin "MH4") (pinfunction "MH4_MH4") (pintype "bidirectional"))
    )
    (net (code "69") (name "unconnected-(U1-ADC6-Pad19)") (class "Default")
      (node (ref "U1") (pin "19") (pinfunction "ADC6_19") (pintype "bidirectional"))
    )
    (net (code "70") (name "unconnected-(U1-ADC7-Pad22)") (class "Default")
      (node (ref "U1") (pin "22") (pinfunction "ADC7_22") (pintype "bidirectional"))
    )
    (net (code "71") (name "unconnected-(U1-PB0(ICP)-Pad12)") (class "Default")
      (node (ref "U1") (pin "12") (pinfunction "PB0(ICP)_12") (pintype "bidirectional"))
    )
    (net (code "72") (name "unconnected-(U1-PB1(OC1A)-Pad13)") (class "Default")
      (node (ref "U1") (pin "13") (pinfunction "PB1(OC1A)_13") (pintype "bidirectional"))
    )
    (net (code "73") (name "unconnected-(U1-PC0(ADC0)-Pad23)") (class "Default")
      (node (ref "U1") (pin "23") (pinfunction "PC0(ADC0)_23") (pintype "bidirectional"))
    )
    (net (code "74") (name "unconnected-(U1-PC1(ADC1)-Pad24)") (class "Default")
      (node (ref "U1") (pin "24") (pinfunction "PC1(ADC1)_24") (pintype "bidirectional"))
    )
    (net (code "75") (name "unconnected-(U1-PC2(ADC2)-Pad25)") (class "Default")
      (node (ref "U1") (pin "25") (pinfunction "PC2(ADC2)_25") (pintype "bidirectional"))
    )
    (net (code "76") (name "unconnected-(U1-PC3(ADC3)-Pad26)") (class "Default")
      (node (ref "U1") (pin "26") (pinfunction "PC3(ADC3)_26") (pintype "bidirectional"))
    )
    (net (code "77") (name "unconnected-(U1-PC4(ADC4{slash}SDA)-Pad27)") (class "Default")
      (node (ref "U1") (pin "27") (pinfunction "PC4(ADC4/SDA)_27") (pintype "bidirectional"))
    )
    (net (code "78") (name "unconnected-(U1-PC5(ADC5{slash}SCL)-Pad28)") (class "Default")
      (node (ref "U1") (pin "28") (pinfunction "PC5(ADC5/SCL)_28") (pintype "bidirectional"))
    )
    (net (code "79") (name "unconnected-(U1-PD0(RXD)-Pad30)") (class "Default")
      (node (ref "U1") (pin "30") (pinfunction "PD0(RXD)_30") (pintype "bidirectional"))
    )
    (net (code "80") (name "unconnected-(U1-PD1(TXD)-Pad31)") (class "Default")
      (node (ref "U1") (pin "31") (pinfunction "PD1(TXD)_31") (pintype "bidirectional"))
    )
    (net (code "81") (name "unconnected-(U1-PD3(INT1)-Pad1)") (class "Default")
      (node (ref "U1") (pin "1") (pinfunction "PD3(INT1)_1") (pintype "bidirectional"))
    )
    (net (code "82") (name "unconnected-(U1-PD4(XCK{slash}T0)-Pad2)") (class "Default")
      (node (ref "U1") (pin "2") (pinfunction "PD4(XCK/T0)_2") (pintype "bidirectional"))
    )
    (net (code "83") (name "unconnected-(U1-PD5(T1)-Pad9)") (class "Default")
      (node (ref "U1") (pin "9") (pinfunction "PD5(T1)_9") (pintype "bidirectional"))
    )
    (net (code "84") (name "unconnected-(U1-PD6(AIN0)-Pad10)") (class "Default")
      (node (ref "U1") (pin "10") (pinfunction "PD6(AIN0)_10") (pintype "bidirectional"))
    )
    (net (code "85") (name "unconnected-(U1-PD7(AIN1)-Pad11)") (class "Default")
      (node (ref "U1") (pin "11") (pinfunction "PD7(AIN1)_11") (pintype "bidirectional"))
    )
    (net (code "86") (name "unconnected-(U2A-CLKOUT-Pad3)") (class "Default")
      (node (ref "U2") (pin "3") (pinfunction "CLKOUT_3") (pintype "output"))
    )
    (net (code "87") (name "unconnected-(U2A-RX0BF-Pad11)") (class "Default")
      (node (ref "U2") (pin "11") (pinfunction "RX0BF_11") (pintype "output"))
    )
    (net (code "88") (name "unconnected-(U2A-RX1BF-Pad10)") (class "Default")
      (node (ref "U2") (pin "10") (pinfunction "RX1BF_10") (pintype "output"))
    )
    (net (code "89") (name "unconnected-(U2A-TX0RTS-Pad4)") (class "Default")
      (node (ref "U2") (pin "4") (pinfunction "TX0RTS_4") (pintype "input"))
    )
    (net (code "90") (name "unconnected-(U2A-TX1RTS-Pad5)") (class "Default")
      (node (ref "U2") (pin "5") (pinfunction "TX1RTS_5") (pintype "input"))
    )
    (net (code "91") (name "unconnected-(U2A-TX2RTS-Pad6)") (class "Default")
      (node (ref "U2") (pin "6") (pinfunction "TX2RTS_6") (pintype "input"))
    )
    (net (code "92") (name "unconnected-(U3-VREF-Pad5)") (class "Default")
      (node (ref "U3") (pin "5") (pinfunction "VREF_5") (pintype "bidirectional"))
    )
    (net (code "93") (name "unconnected-(X1A-KL-Pad1)") (class "Default")
      (node (ref "X1") (pin "1") (pinfunction "KL_1") (pintype "passive"))
    )
    (net (code "94") (name "unconnected-(X1B-KL-Pad2)") (class "Default")
      (node (ref "X1") (pin "2") (pinfunction "KL_2") (pintype "passive"))
    )
  )
)
